# ChargingDock.net
KiCad netlist of a schematic drawn in Altium Designer
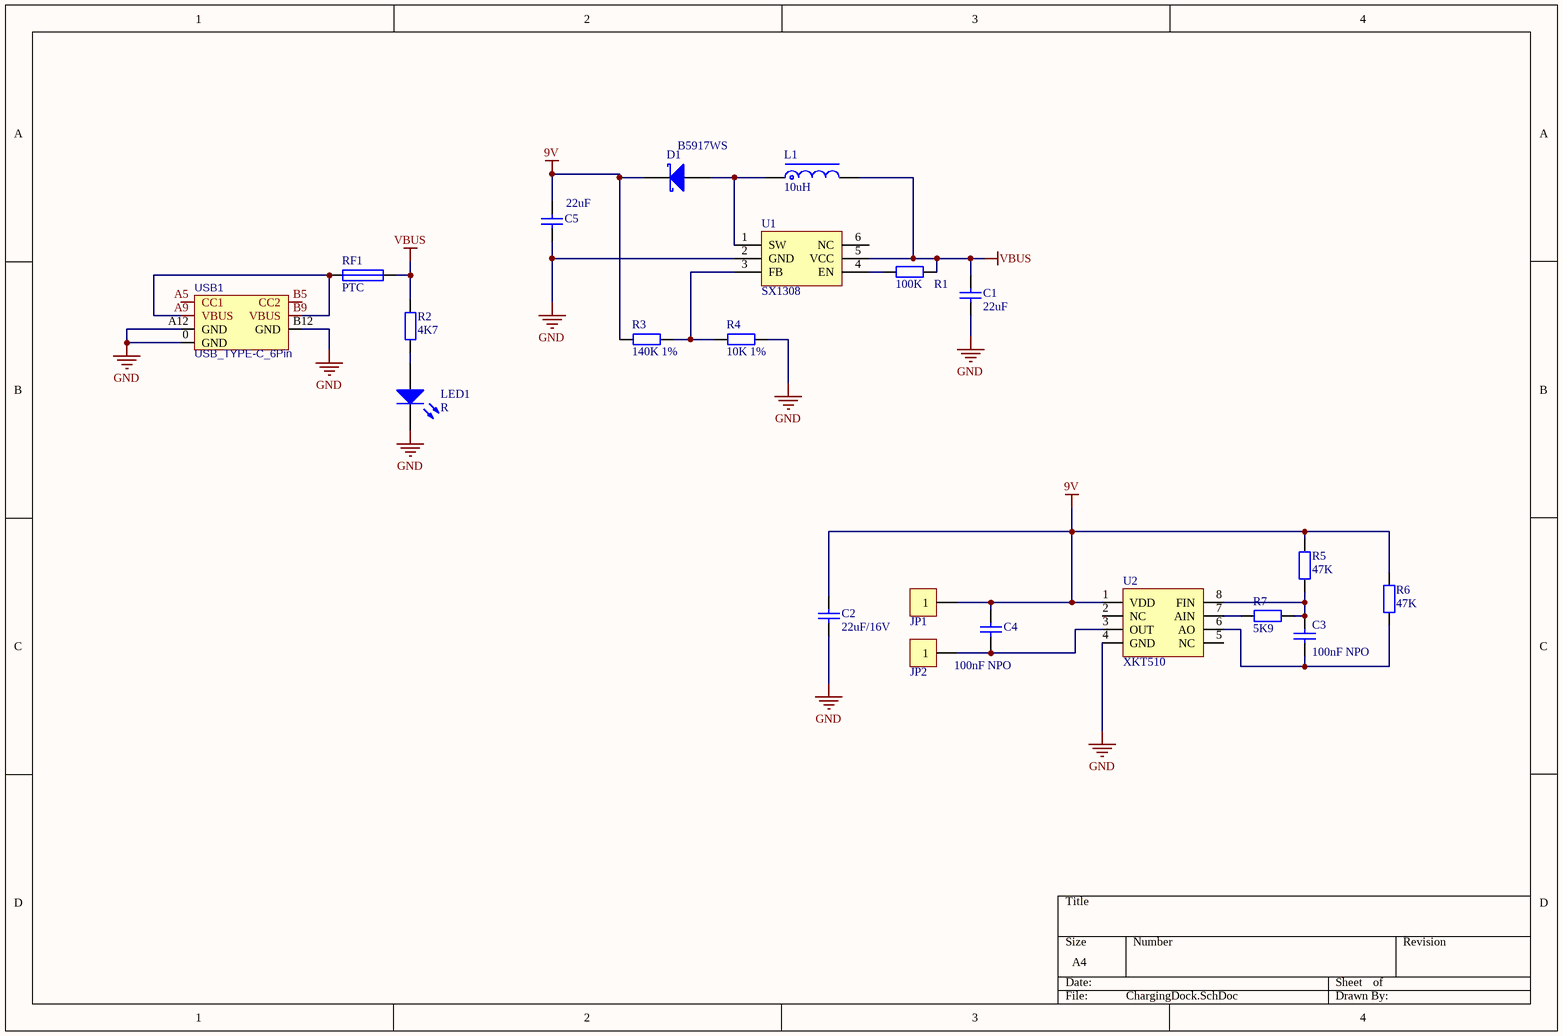
[diagram p0: ChargingDock.SchDoc]

(export (version "E")
  (design (tool "Eeschema 10.0.6"))
  (components
    (comp (ref "C1")
      (value "22uF")
      (footprint "C0805_L")
      (description "贴片电容/MLCC电容")
      (libsource (lib "0.1 - 电阻-电容-电感-晶振-晶体-磁珠-电位器-法拉电容-馈通电容") (part "C"))
    )
    (comp (ref "C2")
      (value "22uF/16V")
      (footprint "C1206_M")
      (description "贴片电容/MLCC电容")
      (libsource (lib "0.1 - 电阻-电容-电感-晶振-晶体-磁珠-电位器-法拉电容-馈通电容") (part "C"))
    )
    (comp (ref "C3")
      (value "100nF NPO")
      (footprint "C0603_M")
      (description "贴片电容/MLCC电容")
      (libsource (lib "0.1 - 电阻-电容-电感-晶振-晶体-磁珠-电位器-法拉电容-馈通电容") (part "C"))
    )
    (comp (ref "C4")
      (value "100nF NPO")
      (footprint "C1206_M")
      (description "贴片电容/MLCC电容")
      (libsource (lib "0.1 - 电阻-电容-电感-晶振-晶体-磁珠-电位器-法拉电容-馈通电容") (part "C"))
    )
    (comp (ref "C5")
      (value "22uF")
      (footprint "C1206_M")
      (description "贴片电容/MLCC电容")
      (libsource (lib "0.1 - 电阻-电容-电感-晶振-晶体-磁珠-电位器-法拉电容-馈通电容") (part "C"))
    )
    (comp (ref "D1")
      (value "B5917WS")
      (footprint "SOD-123")
      (description "肖特基二极管")
      (libsource (lib "0.2 - 二极管-TVS-ESD-整流桥-放电管") (part "1N5817"))
    )
    (comp (ref "JP1")
      (value "HDR-1x1")
      (footprint "HDR2.54-LI-1P")
      (description "1P接插件")
      (libsource (lib "5.5 - 2.54mm连接器(KF2EDGK_XH2.54_2.54排针排母)") (part "Header 1"))
    )
    (comp (ref "JP2")
      (value "HDR-1x1")
      (footprint "HDR2.54-LI-1P")
      (description "1P接插件")
      (libsource (lib "5.5 - 2.54mm连接器(KF2EDGK_XH2.54_2.54排针排母)") (part "Header 1"))
    )
    (comp (ref "L1")
      (value "10uH")
      (footprint "SWPA3015")
      (description "顺络_SWPA贴片屏蔽电感")
      (libsource (lib "0.1 - 电阻-电容-电感-晶振-晶体-磁珠-电位器-法拉电容-馈通电容") (part "L-SWPA"))
    )
    (comp (ref "LED1")
      (value "R")
      (footprint "LED0603_G")
      (description "贴片LED")
      (libsource (lib "0.3 - LED发光二极管-IR二极管_接收管-光耦") (part "LED"))
    )
    (comp (ref "R1")
      (value "100K")
      (footprint "R0603_M")
      (description "贴片电阻")
      (libsource (lib "0.1 - 电阻-电容-电感-晶振-晶体-磁珠-电位器-法拉电容-馈通电容") (part "R"))
    )
    (comp (ref "R2")
      (value "4K7")
      (footprint "R0603_M")
      (description "贴片电阻")
      (libsource (lib "0.1 - 电阻-电容-电感-晶振-晶体-磁珠-电位器-法拉电容-馈通电容") (part "R"))
    )
    (comp (ref "R3")
      (value "140K 1%")
      (footprint "R0603_M")
      (description "贴片电阻")
      (libsource (lib "0.1 - 电阻-电容-电感-晶振-晶体-磁珠-电位器-法拉电容-馈通电容") (part "R"))
    )
    (comp (ref "R4")
      (value "10K 1%")
      (footprint "R0603_M")
      (description "贴片电阻")
      (libsource (lib "0.1 - 电阻-电容-电感-晶振-晶体-磁珠-电位器-法拉电容-馈通电容") (part "R"))
    )
    (comp (ref "R5")
      (value "47K")
      (footprint "R0603_M")
      (description "贴片电阻")
      (libsource (lib "0.1 - 电阻-电容-电感-晶振-晶体-磁珠-电位器-法拉电容-馈通电容") (part "R"))
    )
    (comp (ref "R6")
      (value "47K")
      (footprint "R0603_M")
      (description "贴片电阻")
      (libsource (lib "0.1 - 电阻-电容-电感-晶振-晶体-磁珠-电位器-法拉电容-馈通电容") (part "R"))
    )
    (comp (ref "R7")
      (value "5K9")
      (footprint "R0603_M")
      (description "贴片电阻")
      (libsource (lib "0.1 - 电阻-电容-电感-晶振-晶体-磁珠-电位器-法拉电容-馈通电容") (part "R"))
    )
    (comp (ref "RF1")
      (value "PTC")
      (footprint "FU 1206")
      (description "PPTC贴片自恢复保险丝")
      (libsource (lib "0.5 - 按键_开关_蜂鸣器_保险丝_电池_测试点_Mark点_铜柱") (part "FU-PPTC_SMD"))
    )
    (comp (ref "U1")
      (value "SX1308")
      (footprint "SOT23-6N")
      (description "可调2A升压芯片")
      (libsource (lib "0.7 - 电源类芯片") (part "SX1308"))
    )
    (comp (ref "U2")
      (value "XKT510")
      (footprint "SOP8")
      (description "XKT510无线充充电芯片")
      (libsource (lib "0.7 - 电源类芯片") (part "XKT510"))
    )
    (comp (ref "USB1")
      (value "USB_TYPE-C_6Pin")
      (footprint "USB-C-SMD_6P")
      (description "USB_TYPE-C_6Pin母座")
      (libsource (lib "0.6 - 电源_音频_USB Type-C_HDMI_XT60_5557_D-SUB_RJ45_SD-TF_SIM插座") (part "USB_TYPE-C_6Pin"))
    )
  )
  (nets
    (net (code "1") (name "9V") (class "Default")
      (node (ref "C2") (pin "2") (pinfunction "2_2") (pintype "passive"))
      (node (ref "C4") (pin "2") (pinfunction "2_2") (pintype "passive"))
      (node (ref "C5") (pin "2") (pinfunction "2_2") (pintype "passive"))
      (node (ref "D1") (pin "2") (pinfunction "K_2") (pintype "passive"))
      (node (ref "JP1") (pin "1") (pinfunction "1_1") (pintype "passive"))
      (node (ref "R3") (pin "1") (pinfunction "1_1") (pintype "passive"))
      (node (ref "R5") (pin "2") (pinfunction "2_2") (pintype "passive"))
      (node (ref "R6") (pin "2") (pinfunction "2_2") (pintype "passive"))
      (node (ref "U2") (pin "1") (pinfunction "VDD_1") (pintype "passive"))
    )
    (net (code "2") (name "GND") (class "Default")
      (node (ref "C1") (pin "2") (pinfunction "2_2") (pintype "passive"))
      (node (ref "C2") (pin "1") (pinfunction "1_1") (pintype "passive"))
      (node (ref "C5") (pin "1") (pinfunction "1_1") (pintype "passive"))
      (node (ref "LED1") (pin "2") (pinfunction "K_2") (pintype "passive"))
      (node (ref "R4") (pin "2") (pinfunction "2_2") (pintype "passive"))
      (node (ref "U1") (pin "2") (pinfunction "GND_2") (pintype "passive"))
      (node (ref "U2") (pin "4") (pinfunction "GND_4") (pintype "passive"))
      (node (ref "USB1") (pin "0") (pinfunction "GND_0") (pintype "passive"))
      (node (ref "USB1") (pin "A12") (pinfunction "GND_A12") (pintype "passive"))
      (node (ref "USB1") (pin "B12") (pinfunction "GND_B12") (pintype "passive"))
    )
    (net (code "3") (name "Net-(D1-A)") (class "Default")
      (node (ref "D1") (pin "1") (pinfunction "A_1") (pintype "passive"))
      (node (ref "L1") (pin "1") (pinfunction "1_1") (pintype "passive"))
      (node (ref "U1") (pin "1") (pinfunction "SW_1") (pintype "passive"))
    )
    (net (code "4") (name "Net-(LED1-A)") (class "Default")
      (node (ref "LED1") (pin "1") (pinfunction "A_1") (pintype "passive"))
      (node (ref "R2") (pin "1") (pinfunction "1_1") (pintype "passive"))
    )
    (net (code "5") (name "Net-(RF1-Pad1)") (class "Default")
      (node (ref "RF1") (pin "1") (pinfunction "1_1") (pintype "passive"))
      (node (ref "USB1") (pin "A9") (pinfunction "VBUS_A9") (pintype "passive"))
      (node (ref "USB1") (pin "B9") (pinfunction "VBUS_B9") (pintype "passive"))
    )
    (net (code "6") (name "Net-(U1-EN)") (class "Default")
      (node (ref "R1") (pin "1") (pinfunction "1_1") (pintype "passive"))
      (node (ref "U1") (pin "4") (pinfunction "EN_4") (pintype "passive"))
    )
    (net (code "7") (name "Net-(U1-FB)") (class "Default")
      (node (ref "R3") (pin "2") (pinfunction "2_2") (pintype "passive"))
      (node (ref "R4") (pin "1") (pinfunction "1_1") (pintype "passive"))
      (node (ref "U1") (pin "3") (pinfunction "FB_3") (pintype "passive"))
    )
    (net (code "8") (name "Net-(U2-AIN)") (class "Default")
      (node (ref "R7") (pin "2") (pinfunction "2_2") (pintype "passive"))
      (node (ref "U2") (pin "7") (pinfunction "AIN_7") (pintype "passive"))
    )
    (net (code "9") (name "Net-(U2-AO)") (class "Default")
      (node (ref "C3") (pin "1") (pinfunction "1_1") (pintype "passive"))
      (node (ref "R6") (pin "1") (pinfunction "1_1") (pintype "passive"))
      (node (ref "U2") (pin "6") (pinfunction "AO_6") (pintype "passive"))
    )
    (net (code "10") (name "Net-(U2-FIN)") (class "Default")
      (node (ref "C3") (pin "2") (pinfunction "2_2") (pintype "passive"))
      (node (ref "R5") (pin "1") (pinfunction "1_1") (pintype "passive"))
      (node (ref "R7") (pin "1") (pinfunction "1_1") (pintype "passive"))
      (node (ref "U2") (pin "8") (pinfunction "FIN_8") (pintype "passive"))
    )
    (net (code "11") (name "Net-(U2-OUT)") (class "Default")
      (node (ref "C4") (pin "1") (pinfunction "1_1") (pintype "passive"))
      (node (ref "JP2") (pin "1") (pinfunction "1_1") (pintype "passive"))
      (node (ref "U2") (pin "3") (pinfunction "OUT_3") (pintype "passive"))
    )
    (net (code "12") (name "VBUS") (class "Default")
      (node (ref "C1") (pin "1") (pinfunction "1_1") (pintype "passive"))
      (node (ref "L1") (pin "2") (pinfunction "2_2") (pintype "passive"))
      (node (ref "R1") (pin "2") (pinfunction "2_2") (pintype "passive"))
      (node (ref "R2") (pin "2") (pinfunction "2_2") (pintype "passive"))
      (node (ref "RF1") (pin "2") (pinfunction "2_2") (pintype "passive"))
      (node (ref "U1") (pin "5") (pinfunction "VCC_5") (pintype "passive"))
    )
    (net (code "13") (name "unconnected-(U1-NC-Pad6)") (class "Default")
      (node (ref "U1") (pin "6") (pinfunction "NC_6") (pintype "passive"))
    )
    (net (code "14") (name "unconnected-(U2-NC-Pad2)") (class "Default")
      (node (ref "U2") (pin "2") (pinfunction "NC_2") (pintype "passive"))
    )
    (net (code "15") (name "unconnected-(U2-NC-Pad5)") (class "Default")
      (node (ref "U2") (pin "5") (pinfunction "NC_5") (pintype "passive"))
    )
    (net (code "16") (name "unconnected-(USB1-CC1-PadA5)") (class "Default")
      (node (ref "USB1") (pin "A5") (pinfunction "CC1_A5") (pintype "passive"))
    )
    (net (code "17") (name "unconnected-(USB1-CC2-PadB5)") (class "Default")
      (node (ref "USB1") (pin "B5") (pinfunction "CC2_B5") (pintype "passive"))
    )
  )
)
